# MicroSD.net
KiCad netlist of a schematic drawn in Altium Designer
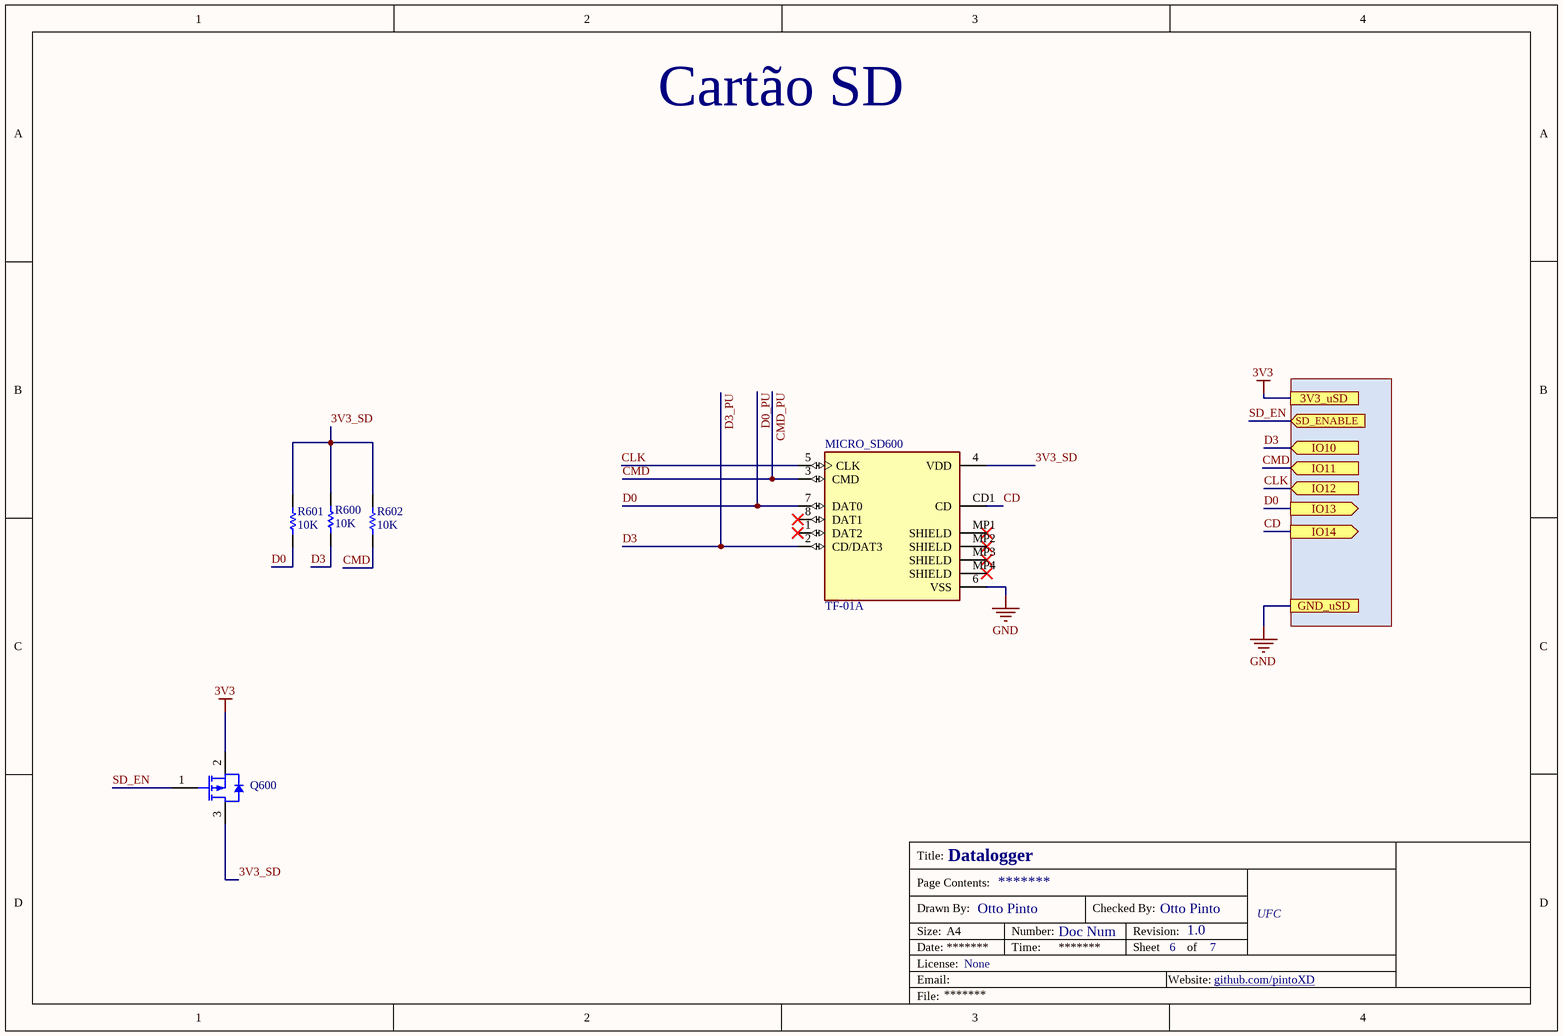
[diagram p0: MicroSD.SchDoc]

(export (version "E")
  (design (tool "Eeschema 10.0.6"))
  (components
    (comp (ref "MICRO_SD600")
      (value "TF-01A")
      (footprint "TF-01A")
      (description "Standard Card Edge Connectors")
      (fields (field (name "MF") "HRO Electronics Co., Ltd."))
      (libsource (lib "Mobit Brasil Ltda") (part "TF-01A"))
    )
    (comp (ref "Q600")
      (value "IC MOSFET P_CHANNEL 20V 6A")
      (footprint "SOT-23")
      (description "Small Low ON Resistance MOSFET P-Channel 20V 6A 3-Pin SOT-23F T/R")
      (fields
        (field (name "MANUFACTURER") "Toshiba")
        (field (name "MANUFACTURER PART NUMBER") "SSM3J358R,LF")
      )
      (libsource (lib "lib_datalogger") (part "IC MOSFET P_CHANNEL 20V 6A"))
    )
    (comp (ref "R600")
      (value "10K")
      (footprint "CR2012-0805")
      (description "RES 0805 10K Ohm 0.1% 1/10W  SMD")
      (fields
        (field (name "MANUFACTURER PART NUMBER") "ERJ-6ENF1002V")
        (field (name "MANUFACTURER") "Panasonic Electronic Components")
        (field (name "SOURCE") "mits.SchLib")
      )
      (libsource (lib "Mobit Brasil Ltda") (part "Symbol"))
    )
    (comp (ref "R601")
      (value "10K")
      (footprint "CR2012-0805")
      (description "RES 0805 10K Ohm 0.1% 1/10W  SMD")
      (fields
        (field (name "MANUFACTURER PART NUMBER") "ERJ-6ENF1002V")
        (field (name "MANUFACTURER") "Panasonic Electronic Components")
        (field (name "SOURCE") "mits.SchLib")
      )
      (libsource (lib "Mobit Brasil Ltda") (part "Symbol"))
    )
    (comp (ref "R602")
      (value "10K")
      (footprint "CR2012-0805")
      (description "RES 0805 10K Ohm 0.1% 1/10W  SMD")
      (fields
        (field (name "MANUFACTURER PART NUMBER") "ERJ-6ENF1002V")
        (field (name "MANUFACTURER") "Panasonic Electronic Components")
        (field (name "SOURCE") "mits.SchLib")
      )
      (libsource (lib "Mobit Brasil Ltda") (part "Symbol"))
    )
  )
  (nets
    (net (code "1") (name "/3V3_SD") (class "Default")
      (node (ref "MICRO_SD600") (pin "4") (pinfunction "VDD_4") (pintype "power_in"))
      (node (ref "Q600") (pin "3") (pinfunction "DRAIN_3") (pintype "passive"))
      (node (ref "R600") (pin "2") (pinfunction "2_2") (pintype "passive"))
      (node (ref "R601") (pin "2") (pinfunction "2_2") (pintype "passive"))
      (node (ref "R602") (pin "2") (pinfunction "2_2") (pintype "passive"))
    )
    (net (code "2") (name "/CD") (class "Default")
      (node (ref "MICRO_SD600") (pin "CD1") (pinfunction "CD_CD1") (pintype "passive"))
    )
    (net (code "3") (name "/CLK") (class "Default")
      (node (ref "MICRO_SD600") (pin "5") (pinfunction "CLK_5") (pintype "bidirectional"))
    )
    (net (code "4") (name "/CMD") (class "Default")
      (node (ref "MICRO_SD600") (pin "3") (pinfunction "CMD_3") (pintype "bidirectional"))
      (node (ref "R602") (pin "1") (pinfunction "1_1") (pintype "passive"))
    )
    (net (code "5") (name "/D0") (class "Default")
      (node (ref "MICRO_SD600") (pin "7") (pinfunction "DAT0_7") (pintype "bidirectional"))
      (node (ref "R601") (pin "1") (pinfunction "1_1") (pintype "passive"))
    )
    (net (code "6") (name "/D3") (class "Default")
      (node (ref "MICRO_SD600") (pin "2") (pinfunction "CD/DAT3_2") (pintype "bidirectional"))
      (node (ref "R600") (pin "1") (pinfunction "1_1") (pintype "passive"))
    )
    (net (code "7") (name "/SD_EN") (class "Default")
      (node (ref "Q600") (pin "1") (pinfunction "GATE_1") (pintype "passive"))
    )
    (net (code "8") (name "3V3") (class "Default")
      (node (ref "Q600") (pin "2") (pinfunction "SOURCE_2") (pintype "passive"))
    )
    (net (code "9") (name "GND") (class "Default")
      (node (ref "MICRO_SD600") (pin "6") (pinfunction "VSS_6") (pintype "power_in"))
    )
    (net (code "10") (name "unconnected-(MICRO_SD600-DAT1-Pad8)") (class "Default")
      (node (ref "MICRO_SD600") (pin "8") (pinfunction "DAT1_8") (pintype "bidirectional+no_connect"))
    )
    (net (code "11") (name "unconnected-(MICRO_SD600-DAT2-Pad1)") (class "Default")
      (node (ref "MICRO_SD600") (pin "1") (pinfunction "DAT2_1") (pintype "bidirectional+no_connect"))
    )
    (net (code "12") (name "unconnected-(MICRO_SD600-SHIELD-PadMP1)") (class "Default")
      (node (ref "MICRO_SD600") (pin "MP1") (pinfunction "SHIELD_MP1") (pintype "power_in+no_connect"))
    )
    (net (code "13") (name "unconnected-(MICRO_SD600-SHIELD-PadMP2)") (class "Default")
      (node (ref "MICRO_SD600") (pin "MP2") (pinfunction "SHIELD_MP2") (pintype "power_in+no_connect"))
    )
    (net (code "14") (name "unconnected-(MICRO_SD600-SHIELD-PadMP3)") (class "Default")
      (node (ref "MICRO_SD600") (pin "MP3") (pinfunction "SHIELD_MP3") (pintype "power_in+no_connect"))
    )
    (net (code "15") (name "unconnected-(MICRO_SD600-SHIELD-PadMP4)") (class "Default")
      (node (ref "MICRO_SD600") (pin "MP4") (pinfunction "SHIELD_MP4") (pintype "power_in+no_connect"))
    )
  )
)
